# ALU.net
KiCad netlist of a schematic drawn in EAGLE
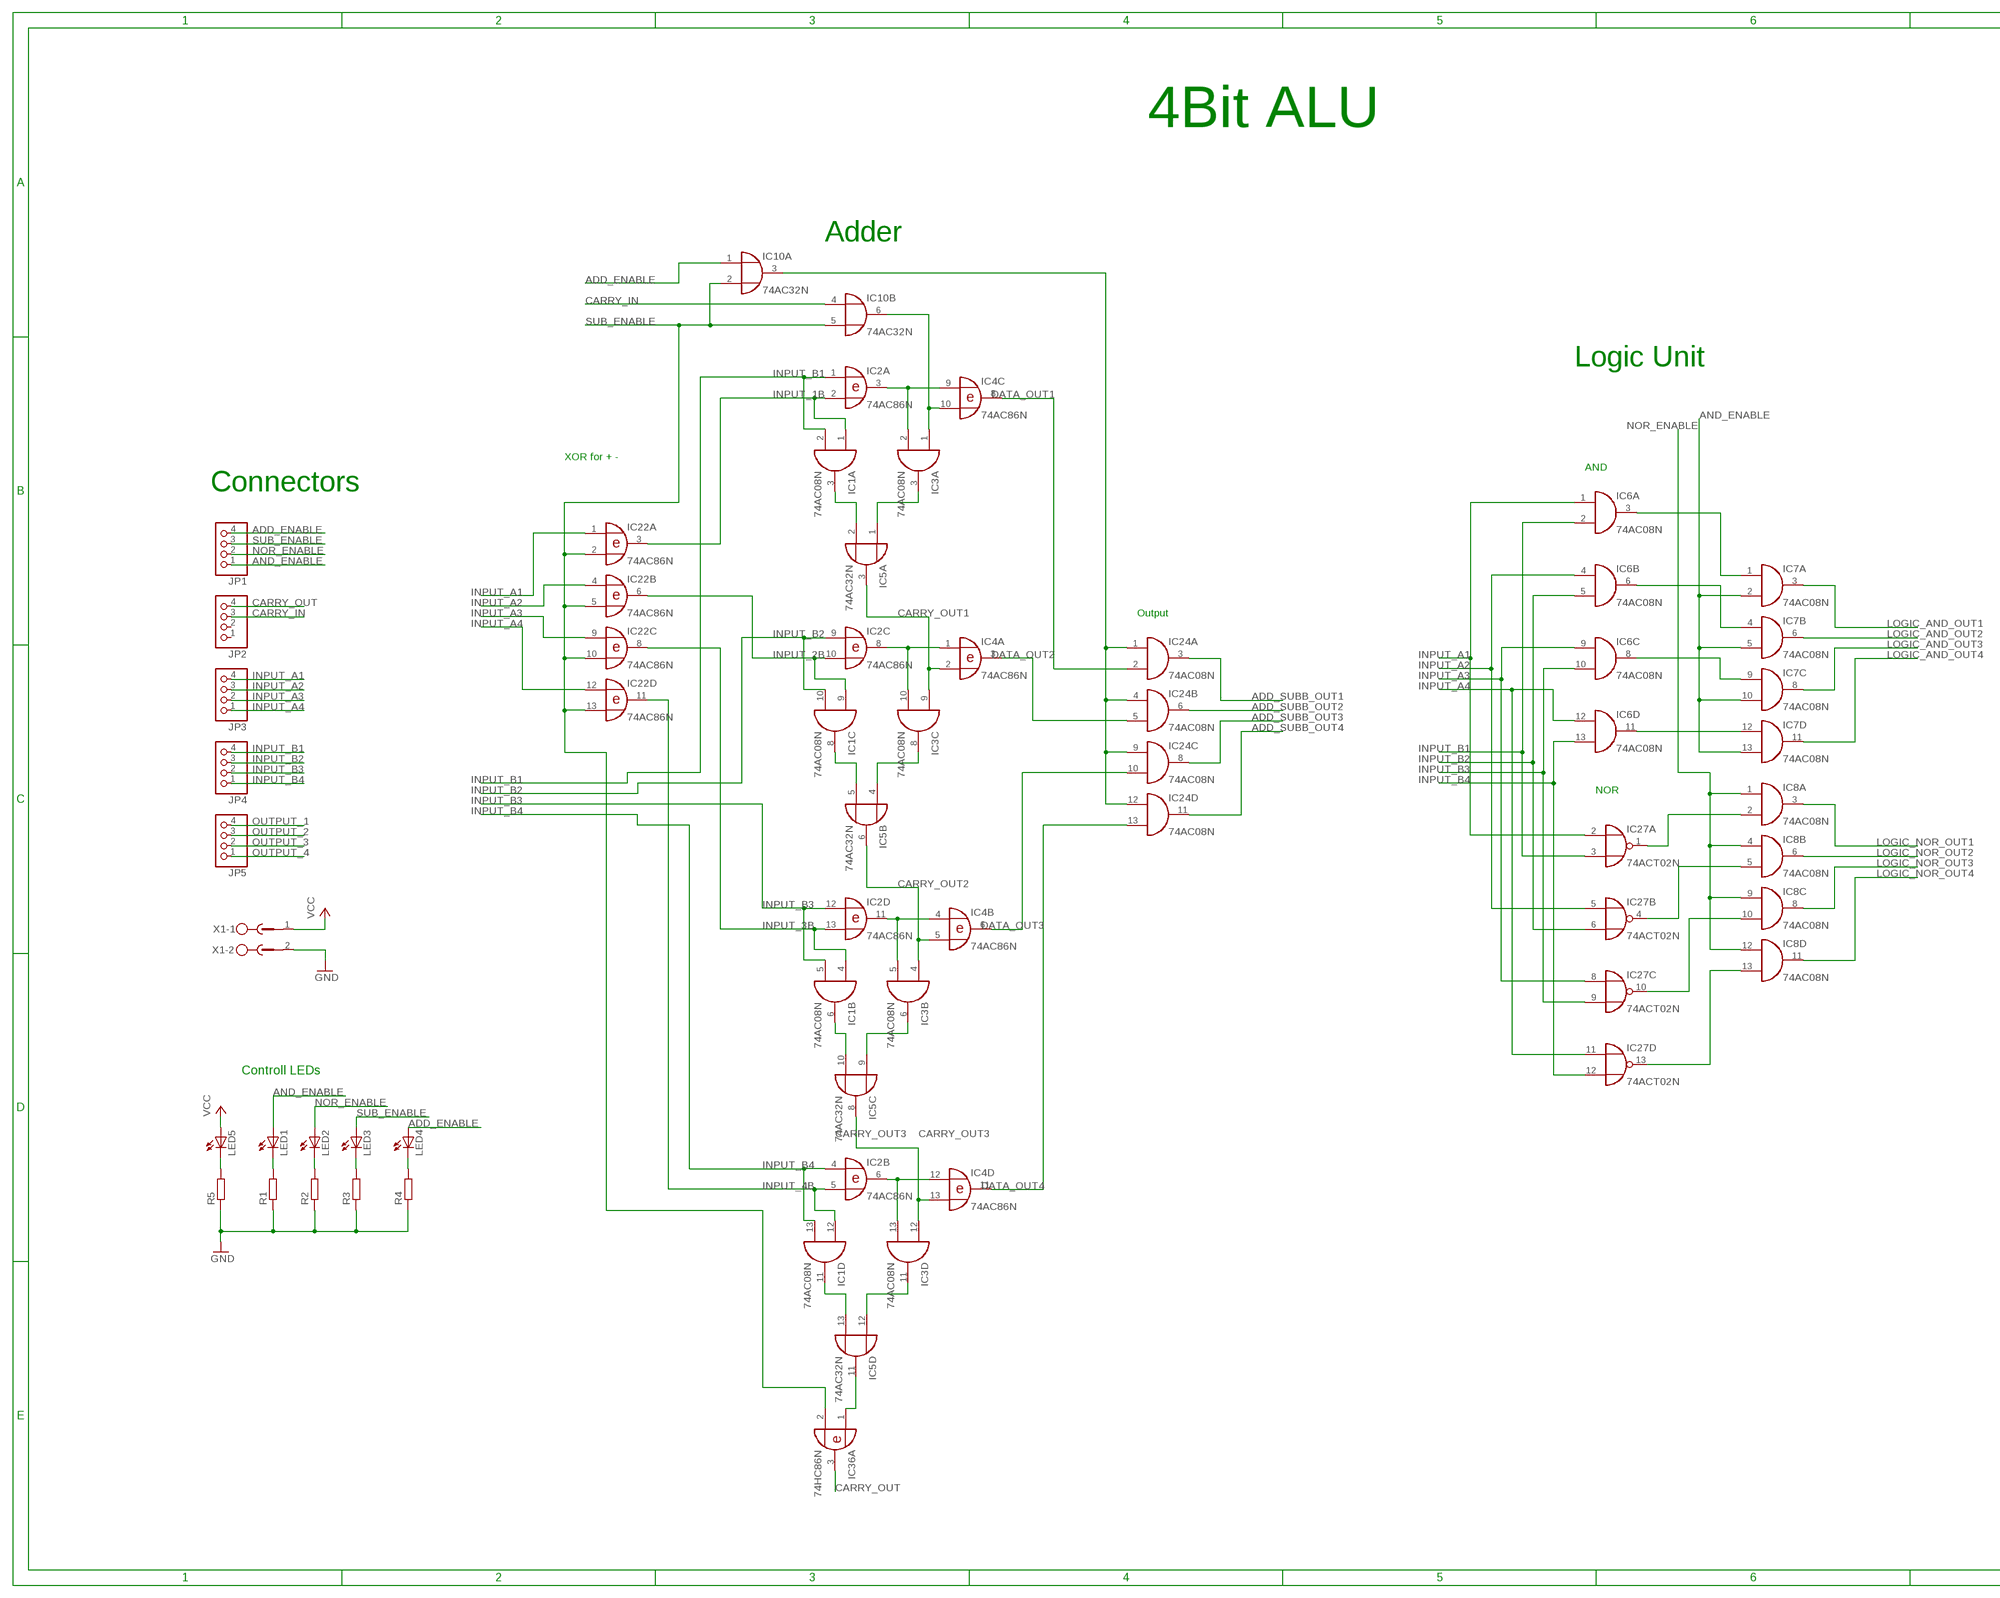
[diagram p0: schematic, sheet 1, part 1 of 2]
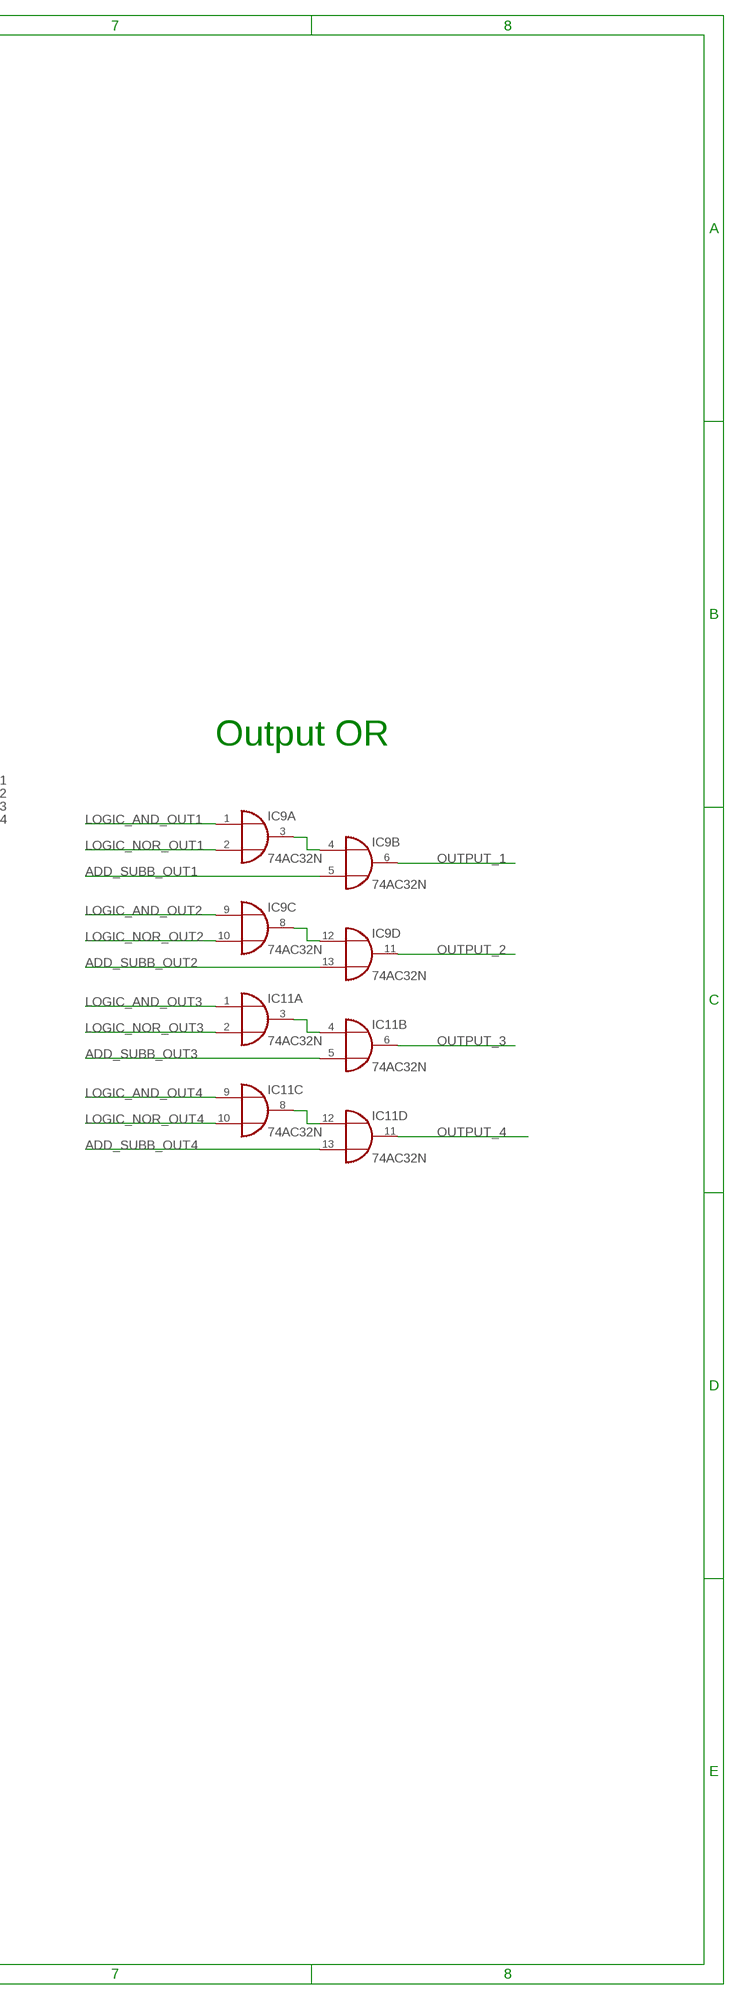
[diagram p1: schematic, sheet 1, part 2 of 2]

(export (version "E")
  (design (tool "Eeschema 10.0.6"))
  (components
    (comp (ref "IC1")
      (value "74AC08N")
      (footprint "eagle-import:DIL14")
      (libsource (lib "eagle-import") (part "7408NAC"))
    )
    (comp (ref "IC2")
      (value "74AC86N")
      (footprint "eagle-import:DIL14")
      (libsource (lib "eagle-import") (part "7486NAC"))
    )
    (comp (ref "IC3")
      (value "74AC08N")
      (footprint "eagle-import:DIL14")
      (libsource (lib "eagle-import") (part "7408NAC"))
    )
    (comp (ref "IC4")
      (value "74AC86N")
      (footprint "eagle-import:DIL14")
      (libsource (lib "eagle-import") (part "7486NAC"))
    )
    (comp (ref "IC5")
      (value "74AC32N")
      (footprint "eagle-import:DIL14")
      (libsource (lib "eagle-import") (part "7432NAC"))
    )
    (comp (ref "IC6")
      (value "74AC08N")
      (footprint "eagle-import:DIL14")
      (libsource (lib "eagle-import") (part "7408NAC"))
    )
    (comp (ref "IC7")
      (value "74AC08N")
      (footprint "eagle-import:DIL14")
      (libsource (lib "eagle-import") (part "7408NAC"))
    )
    (comp (ref "IC8")
      (value "74AC08N")
      (footprint "eagle-import:DIL14")
      (libsource (lib "eagle-import") (part "7408NAC"))
    )
    (comp (ref "IC9")
      (value "74AC32N")
      (footprint "eagle-import:DIL14")
      (libsource (lib "eagle-import") (part "7432NAC"))
    )
    (comp (ref "IC10")
      (value "74AC32N")
      (footprint "eagle-import:DIL14")
      (libsource (lib "eagle-import") (part "7432NAC"))
    )
    (comp (ref "IC11")
      (value "74AC32N")
      (footprint "eagle-import:DIL14")
      (libsource (lib "eagle-import") (part "7432NAC"))
    )
    (comp (ref "IC22")
      (value "74AC86N")
      (footprint "eagle-import:DIL14")
      (libsource (lib "eagle-import") (part "7486NAC"))
    )
    (comp (ref "IC24")
      (value "74AC08N")
      (footprint "eagle-import:DIL14")
      (libsource (lib "eagle-import") (part "7408NAC"))
    )
    (comp (ref "IC27")
      (value "74ACT02N")
      (footprint "eagle-import:DIL14")
      (libsource (lib "eagle-import") (part "7402NACT"))
    )
    (comp (ref "IC36")
      (value "74HC86N")
      (footprint "eagle-import:DIL14")
      (libsource (lib "eagle-import") (part "7486NHC"))
    )
    (comp (ref "JP1")
      (value "PINHD-1X4")
      (footprint "eagle-import:1X04")
      (libsource (lib "eagle-import") (part "PINHD-1X4"))
    )
    (comp (ref "JP2")
      (value "PINHD-1X4")
      (footprint "eagle-import:1X04")
      (libsource (lib "eagle-import") (part "PINHD-1X4"))
    )
    (comp (ref "JP3")
      (value "PINHD-1X4")
      (footprint "eagle-import:1X04")
      (libsource (lib "eagle-import") (part "PINHD-1X4"))
    )
    (comp (ref "JP4")
      (value "PINHD-1X4")
      (footprint "eagle-import:1X04")
      (libsource (lib "eagle-import") (part "PINHD-1X4"))
    )
    (comp (ref "JP5")
      (value "PINHD-1X4")
      (footprint "eagle-import:1X04")
      (libsource (lib "eagle-import") (part "PINHD-1X4"))
    )
    (comp (ref "LED1")
      (value "LED5MM")
      (footprint "eagle-import:LED5MM")
      (libsource (lib "eagle-import") (part "LED5MM"))
    )
    (comp (ref "LED2")
      (value "LED5MM")
      (footprint "eagle-import:LED5MM")
      (libsource (lib "eagle-import") (part "LED5MM"))
    )
    (comp (ref "LED3")
      (value "LED5MM")
      (footprint "eagle-import:LED5MM")
      (libsource (lib "eagle-import") (part "LED5MM"))
    )
    (comp (ref "LED4")
      (value "LED5MM")
      (footprint "eagle-import:LED5MM")
      (libsource (lib "eagle-import") (part "LED5MM"))
    )
    (comp (ref "LED5")
      (value "LED5MM")
      (footprint "eagle-import:LED5MM")
      (libsource (lib "eagle-import") (part "LED5MM"))
    )
    (comp (ref "R1")
      (value "R-EU_0204/5")
      (footprint "eagle-import:0204_5")
      (libsource (lib "eagle-import") (part "R-EU_0204/5"))
    )
    (comp (ref "R2")
      (value "R-EU_0204/5")
      (footprint "eagle-import:0204_5")
      (libsource (lib "eagle-import") (part "R-EU_0204/5"))
    )
    (comp (ref "R3")
      (value "R-EU_0204/5")
      (footprint "eagle-import:0204_5")
      (libsource (lib "eagle-import") (part "R-EU_0204/5"))
    )
    (comp (ref "R4")
      (value "R-EU_0204/5")
      (footprint "eagle-import:0204_5")
      (libsource (lib "eagle-import") (part "R-EU_0204/5"))
    )
    (comp (ref "R5")
      (value "R-EU_0204/5")
      (footprint "eagle-import:0204_5")
      (libsource (lib "eagle-import") (part "R-EU_0204/5"))
    )
    (comp (ref "X1")
      (value "MSTBV2")
      (footprint "eagle-import:MSTBV2")
      (libsource (lib "eagle-import") (part "MSTBV2"))
    )
  )
  (nets
    (net (code "1") (name "/ADD_ENABLE") (class "Default")
      (node (ref "IC10") (pin "1") (pinfunction "I0_1") (pintype "input"))
      (node (ref "JP1") (pin "4") (pinfunction "4_4") (pintype "passive"))
      (node (ref "LED4") (pin "A") (pinfunction "A_A") (pintype "passive"))
    )
    (net (code "2") (name "/ADD_SUBB_OUT1") (class "Default")
      (node (ref "IC24") (pin "3") (pinfunction "O_3") (pintype "output"))
      (node (ref "IC9") (pin "5") (pinfunction "I1_5") (pintype "input"))
    )
    (net (code "3") (name "/ADD_SUBB_OUT2") (class "Default")
      (node (ref "IC24") (pin "6") (pinfunction "O_6") (pintype "output"))
      (node (ref "IC9") (pin "13") (pinfunction "I1_13") (pintype "input"))
    )
    (net (code "4") (name "/ADD_SUBB_OUT3") (class "Default")
      (node (ref "IC11") (pin "5") (pinfunction "I1_5") (pintype "input"))
      (node (ref "IC24") (pin "8") (pinfunction "O_8") (pintype "output"))
    )
    (net (code "5") (name "/ADD_SUBB_OUT4") (class "Default")
      (node (ref "IC11") (pin "13") (pinfunction "I1_13") (pintype "input"))
      (node (ref "IC24") (pin "11") (pinfunction "O_11") (pintype "output"))
    )
    (net (code "6") (name "/AND_ENABLE") (class "Default")
      (node (ref "IC7") (pin "10") (pinfunction "I1_10") (pintype "input"))
      (node (ref "IC7") (pin "13") (pinfunction "I1_13") (pintype "input"))
      (node (ref "IC7") (pin "2") (pinfunction "I1_2") (pintype "input"))
      (node (ref "IC7") (pin "5") (pinfunction "I1_5") (pintype "input"))
      (node (ref "JP1") (pin "1") (pinfunction "1_1") (pintype "passive"))
      (node (ref "LED1") (pin "A") (pinfunction "A_A") (pintype "passive"))
    )
    (net (code "7") (name "/CARRY_IN") (class "Default")
      (node (ref "IC10") (pin "4") (pinfunction "I0_4") (pintype "input"))
      (node (ref "JP2") (pin "3") (pinfunction "3_3") (pintype "passive"))
    )
    (net (code "8") (name "/CARRY_OUT") (class "Default")
      (node (ref "IC36") (pin "3") (pinfunction "O_3") (pintype "output"))
      (node (ref "JP2") (pin "4") (pinfunction "4_4") (pintype "passive"))
    )
    (net (code "9") (name "/CARRY_OUT1") (class "Default")
      (node (ref "IC3") (pin "9") (pinfunction "I0_9") (pintype "input"))
      (node (ref "IC4") (pin "2") (pinfunction "I1_2") (pintype "input"))
      (node (ref "IC5") (pin "3") (pinfunction "O_3") (pintype "output"))
    )
    (net (code "10") (name "/CARRY_OUT2") (class "Default")
      (node (ref "IC3") (pin "4") (pinfunction "I0_4") (pintype "input"))
      (node (ref "IC4") (pin "5") (pinfunction "I1_5") (pintype "input"))
      (node (ref "IC5") (pin "6") (pinfunction "O_6") (pintype "output"))
    )
    (net (code "11") (name "/CARRY_OUT3") (class "Default")
      (node (ref "IC3") (pin "12") (pinfunction "I0_12") (pintype "input"))
      (node (ref "IC4") (pin "13") (pinfunction "I1_13") (pintype "input"))
      (node (ref "IC5") (pin "8") (pinfunction "O_8") (pintype "output"))
    )
    (net (code "12") (name "/DATA_OUT1") (class "Default")
      (node (ref "IC24") (pin "2") (pinfunction "I1_2") (pintype "input"))
      (node (ref "IC4") (pin "8") (pinfunction "O_8") (pintype "output"))
    )
    (net (code "13") (name "/DATA_OUT2") (class "Default")
      (node (ref "IC24") (pin "5") (pinfunction "I1_5") (pintype "input"))
      (node (ref "IC4") (pin "3") (pinfunction "O_3") (pintype "output"))
    )
    (net (code "14") (name "/DATA_OUT3") (class "Default")
      (node (ref "IC24") (pin "10") (pinfunction "I1_10") (pintype "input"))
      (node (ref "IC4") (pin "6") (pinfunction "O_6") (pintype "output"))
    )
    (net (code "15") (name "/DATA_OUT4") (class "Default")
      (node (ref "IC24") (pin "13") (pinfunction "I1_13") (pintype "input"))
      (node (ref "IC4") (pin "11") (pinfunction "O_11") (pintype "output"))
    )
    (net (code "16") (name "/INPUT_1B") (class "Default")
      (node (ref "IC1") (pin "1") (pinfunction "I0_1") (pintype "input"))
      (node (ref "IC2") (pin "2") (pinfunction "I1_2") (pintype "input"))
      (node (ref "IC22") (pin "3") (pinfunction "O_3") (pintype "output"))
    )
    (net (code "17") (name "/INPUT_2B") (class "Default")
      (node (ref "IC1") (pin "9") (pinfunction "I0_9") (pintype "input"))
      (node (ref "IC2") (pin "10") (pinfunction "I1_10") (pintype "input"))
      (node (ref "IC22") (pin "6") (pinfunction "O_6") (pintype "output"))
    )
    (net (code "18") (name "/INPUT_3B") (class "Default")
      (node (ref "IC1") (pin "4") (pinfunction "I0_4") (pintype "input"))
      (node (ref "IC2") (pin "13") (pinfunction "I1_13") (pintype "input"))
      (node (ref "IC22") (pin "8") (pinfunction "O_8") (pintype "output"))
    )
    (net (code "19") (name "/INPUT_4B") (class "Default")
      (node (ref "IC1") (pin "12") (pinfunction "I0_12") (pintype "input"))
      (node (ref "IC2") (pin "5") (pinfunction "I1_5") (pintype "input"))
      (node (ref "IC22") (pin "11") (pinfunction "O_11") (pintype "output"))
    )
    (net (code "20") (name "/INPUT_A1") (class "Default")
      (node (ref "IC22") (pin "1") (pinfunction "I0_1") (pintype "input"))
      (node (ref "IC27") (pin "2") (pinfunction "I0_2") (pintype "input"))
      (node (ref "IC6") (pin "1") (pinfunction "I0_1") (pintype "input"))
      (node (ref "JP3") (pin "4") (pinfunction "4_4") (pintype "passive"))
    )
    (net (code "21") (name "/INPUT_A2") (class "Default")
      (node (ref "IC22") (pin "4") (pinfunction "I0_4") (pintype "input"))
      (node (ref "IC27") (pin "5") (pinfunction "I0_5") (pintype "input"))
      (node (ref "IC6") (pin "4") (pinfunction "I0_4") (pintype "input"))
      (node (ref "JP3") (pin "3") (pinfunction "3_3") (pintype "passive"))
    )
    (net (code "22") (name "/INPUT_A3") (class "Default")
      (node (ref "IC22") (pin "9") (pinfunction "I0_9") (pintype "input"))
      (node (ref "IC27") (pin "8") (pinfunction "I0_8") (pintype "input"))
      (node (ref "IC6") (pin "9") (pinfunction "I0_9") (pintype "input"))
      (node (ref "JP3") (pin "2") (pinfunction "2_2") (pintype "passive"))
    )
    (net (code "23") (name "/INPUT_A4") (class "Default")
      (node (ref "IC22") (pin "12") (pinfunction "I0_12") (pintype "input"))
      (node (ref "IC27") (pin "11") (pinfunction "I0_11") (pintype "input"))
      (node (ref "IC6") (pin "12") (pinfunction "I0_12") (pintype "input"))
      (node (ref "JP3") (pin "1") (pinfunction "1_1") (pintype "passive"))
    )
    (net (code "24") (name "/INPUT_B1") (class "Default")
      (node (ref "IC1") (pin "2") (pinfunction "I1_2") (pintype "input"))
      (node (ref "IC2") (pin "1") (pinfunction "I0_1") (pintype "input"))
      (node (ref "IC27") (pin "3") (pinfunction "I1_3") (pintype "input"))
      (node (ref "IC6") (pin "2") (pinfunction "I1_2") (pintype "input"))
      (node (ref "JP4") (pin "4") (pinfunction "4_4") (pintype "passive"))
    )
    (net (code "25") (name "/INPUT_B2") (class "Default")
      (node (ref "IC1") (pin "10") (pinfunction "I1_10") (pintype "input"))
      (node (ref "IC2") (pin "9") (pinfunction "I0_9") (pintype "input"))
      (node (ref "IC27") (pin "6") (pinfunction "I1_6") (pintype "input"))
      (node (ref "IC6") (pin "5") (pinfunction "I1_5") (pintype "input"))
      (node (ref "JP4") (pin "3") (pinfunction "3_3") (pintype "passive"))
    )
    (net (code "26") (name "/INPUT_B3") (class "Default")
      (node (ref "IC1") (pin "5") (pinfunction "I1_5") (pintype "input"))
      (node (ref "IC2") (pin "12") (pinfunction "I0_12") (pintype "input"))
      (node (ref "IC27") (pin "9") (pinfunction "I1_9") (pintype "input"))
      (node (ref "IC6") (pin "10") (pinfunction "I1_10") (pintype "input"))
      (node (ref "JP4") (pin "2") (pinfunction "2_2") (pintype "passive"))
    )
    (net (code "27") (name "/INPUT_B4") (class "Default")
      (node (ref "IC1") (pin "13") (pinfunction "I1_13") (pintype "input"))
      (node (ref "IC2") (pin "4") (pinfunction "I0_4") (pintype "input"))
      (node (ref "IC27") (pin "12") (pinfunction "I1_12") (pintype "input"))
      (node (ref "IC6") (pin "13") (pinfunction "I1_13") (pintype "input"))
      (node (ref "JP4") (pin "1") (pinfunction "1_1") (pintype "passive"))
    )
    (net (code "28") (name "/LOGIC_AND_OUT1") (class "Default")
      (node (ref "IC7") (pin "3") (pinfunction "O_3") (pintype "output"))
      (node (ref "IC9") (pin "1") (pinfunction "I0_1") (pintype "input"))
    )
    (net (code "29") (name "/LOGIC_AND_OUT2") (class "Default")
      (node (ref "IC7") (pin "6") (pinfunction "O_6") (pintype "output"))
      (node (ref "IC9") (pin "9") (pinfunction "I0_9") (pintype "input"))
    )
    (net (code "30") (name "/LOGIC_AND_OUT3") (class "Default")
      (node (ref "IC11") (pin "1") (pinfunction "I0_1") (pintype "input"))
      (node (ref "IC7") (pin "8") (pinfunction "O_8") (pintype "output"))
    )
    (net (code "31") (name "/LOGIC_AND_OUT4") (class "Default")
      (node (ref "IC11") (pin "9") (pinfunction "I0_9") (pintype "input"))
      (node (ref "IC7") (pin "11") (pinfunction "O_11") (pintype "output"))
    )
    (net (code "32") (name "/LOGIC_NOR_OUT1") (class "Default")
      (node (ref "IC8") (pin "3") (pinfunction "O_3") (pintype "output"))
      (node (ref "IC9") (pin "2") (pinfunction "I1_2") (pintype "input"))
    )
    (net (code "33") (name "/LOGIC_NOR_OUT2") (class "Default")
      (node (ref "IC8") (pin "6") (pinfunction "O_6") (pintype "output"))
      (node (ref "IC9") (pin "10") (pinfunction "I1_10") (pintype "input"))
    )
    (net (code "34") (name "/LOGIC_NOR_OUT3") (class "Default")
      (node (ref "IC11") (pin "2") (pinfunction "I1_2") (pintype "input"))
      (node (ref "IC8") (pin "8") (pinfunction "O_8") (pintype "output"))
    )
    (net (code "35") (name "/LOGIC_NOR_OUT4") (class "Default")
      (node (ref "IC11") (pin "10") (pinfunction "I1_10") (pintype "input"))
      (node (ref "IC8") (pin "11") (pinfunction "O_11") (pintype "output"))
    )
    (net (code "36") (name "/NOR_ENABLE") (class "Default")
      (node (ref "IC8") (pin "1") (pinfunction "I0_1") (pintype "input"))
      (node (ref "IC8") (pin "12") (pinfunction "I0_12") (pintype "input"))
      (node (ref "IC8") (pin "4") (pinfunction "I0_4") (pintype "input"))
      (node (ref "IC8") (pin "9") (pinfunction "I0_9") (pintype "input"))
      (node (ref "JP1") (pin "2") (pinfunction "2_2") (pintype "passive"))
      (node (ref "LED2") (pin "A") (pinfunction "A_A") (pintype "passive"))
    )
    (net (code "37") (name "/OUTPUT_1") (class "Default")
      (node (ref "IC9") (pin "6") (pinfunction "O_6") (pintype "output"))
      (node (ref "JP5") (pin "4") (pinfunction "4_4") (pintype "passive"))
    )
    (net (code "38") (name "/OUTPUT_2") (class "Default")
      (node (ref "IC9") (pin "11") (pinfunction "O_11") (pintype "output"))
      (node (ref "JP5") (pin "3") (pinfunction "3_3") (pintype "passive"))
    )
    (net (code "39") (name "/OUTPUT_3") (class "Default")
      (node (ref "IC11") (pin "6") (pinfunction "O_6") (pintype "output"))
      (node (ref "JP5") (pin "2") (pinfunction "2_2") (pintype "passive"))
    )
    (net (code "40") (name "/OUTPUT_4") (class "Default")
      (node (ref "IC11") (pin "11") (pinfunction "O_11") (pintype "output"))
      (node (ref "JP5") (pin "1") (pinfunction "1_1") (pintype "passive"))
    )
    (net (code "41") (name "/SUB_ENABLE") (class "Default")
      (node (ref "IC10") (pin "2") (pinfunction "I1_2") (pintype "input"))
      (node (ref "IC10") (pin "5") (pinfunction "I1_5") (pintype "input"))
      (node (ref "IC22") (pin "10") (pinfunction "I1_10") (pintype "input"))
      (node (ref "IC22") (pin "13") (pinfunction "I1_13") (pintype "input"))
      (node (ref "IC22") (pin "2") (pinfunction "I1_2") (pintype "input"))
      (node (ref "IC22") (pin "5") (pinfunction "I1_5") (pintype "input"))
      (node (ref "IC36") (pin "2") (pinfunction "I1_2") (pintype "input"))
      (node (ref "JP1") (pin "3") (pinfunction "3_3") (pintype "passive"))
      (node (ref "LED3") (pin "A") (pinfunction "A_A") (pintype "passive"))
    )
    (net (code "42") (name "GND") (class "Default")
      (node (ref "R1") (pin "1") (pinfunction "1_1") (pintype "passive"))
      (node (ref "R2") (pin "1") (pinfunction "1_1") (pintype "passive"))
      (node (ref "R3") (pin "1") (pinfunction "1_1") (pintype "passive"))
      (node (ref "R4") (pin "1") (pinfunction "1_1") (pintype "passive"))
      (node (ref "R5") (pin "1") (pinfunction "1_1") (pintype "passive"))
      (node (ref "X1") (pin "2") (pinfunction "SK_2") (pintype "passive"))
    )
    (net (code "43") (name "Net-(IC1A-O)") (class "Default")
      (node (ref "IC1") (pin "3") (pinfunction "O_3") (pintype "output"))
      (node (ref "IC5") (pin "2") (pinfunction "I1_2") (pintype "input"))
    )
    (net (code "44") (name "Net-(IC1B-O)") (class "Default")
      (node (ref "IC1") (pin "6") (pinfunction "O_6") (pintype "output"))
      (node (ref "IC5") (pin "10") (pinfunction "I1_10") (pintype "input"))
    )
    (net (code "45") (name "Net-(IC1C-O)") (class "Default")
      (node (ref "IC1") (pin "8") (pinfunction "O_8") (pintype "output"))
      (node (ref "IC5") (pin "5") (pinfunction "I1_5") (pintype "input"))
    )
    (net (code "46") (name "Net-(IC1D-O)") (class "Default")
      (node (ref "IC1") (pin "11") (pinfunction "O_11") (pintype "output"))
      (node (ref "IC5") (pin "13") (pinfunction "I1_13") (pintype "input"))
    )
    (net (code "47") (name "Net-(IC2A-O)") (class "Default")
      (node (ref "IC2") (pin "3") (pinfunction "O_3") (pintype "output"))
      (node (ref "IC3") (pin "2") (pinfunction "I1_2") (pintype "input"))
      (node (ref "IC4") (pin "9") (pinfunction "I0_9") (pintype "input"))
    )
    (net (code "48") (name "Net-(IC2B-O)") (class "Default")
      (node (ref "IC2") (pin "6") (pinfunction "O_6") (pintype "output"))
      (node (ref "IC3") (pin "13") (pinfunction "I1_13") (pintype "input"))
      (node (ref "IC4") (pin "12") (pinfunction "I0_12") (pintype "input"))
    )
    (net (code "49") (name "Net-(IC2C-O)") (class "Default")
      (node (ref "IC2") (pin "8") (pinfunction "O_8") (pintype "output"))
      (node (ref "IC3") (pin "10") (pinfunction "I1_10") (pintype "input"))
      (node (ref "IC4") (pin "1") (pinfunction "I0_1") (pintype "input"))
    )
    (net (code "50") (name "Net-(IC2D-O)") (class "Default")
      (node (ref "IC2") (pin "11") (pinfunction "O_11") (pintype "output"))
      (node (ref "IC3") (pin "5") (pinfunction "I1_5") (pintype "input"))
      (node (ref "IC4") (pin "4") (pinfunction "I0_4") (pintype "input"))
    )
    (net (code "51") (name "Net-(IC3A-O)") (class "Default")
      (node (ref "IC3") (pin "3") (pinfunction "O_3") (pintype "output"))
      (node (ref "IC5") (pin "1") (pinfunction "I0_1") (pintype "input"))
    )
    (net (code "52") (name "Net-(IC3B-O)") (class "Default")
      (node (ref "IC3") (pin "6") (pinfunction "O_6") (pintype "output"))
      (node (ref "IC5") (pin "9") (pinfunction "I0_9") (pintype "input"))
    )
    (net (code "53") (name "Net-(IC3C-O)") (class "Default")
      (node (ref "IC3") (pin "8") (pinfunction "O_8") (pintype "output"))
      (node (ref "IC5") (pin "4") (pinfunction "I0_4") (pintype "input"))
    )
    (net (code "54") (name "Net-(IC3D-O)") (class "Default")
      (node (ref "IC3") (pin "11") (pinfunction "O_11") (pintype "output"))
      (node (ref "IC5") (pin "12") (pinfunction "I0_12") (pintype "input"))
    )
    (net (code "55") (name "Net-(IC6A-O)") (class "Default")
      (node (ref "IC6") (pin "3") (pinfunction "O_3") (pintype "output"))
      (node (ref "IC7") (pin "1") (pinfunction "I0_1") (pintype "input"))
    )
    (net (code "56") (name "Net-(IC6B-O)") (class "Default")
      (node (ref "IC6") (pin "6") (pinfunction "O_6") (pintype "output"))
      (node (ref "IC7") (pin "4") (pinfunction "I0_4") (pintype "input"))
    )
    (net (code "57") (name "Net-(IC6C-O)") (class "Default")
      (node (ref "IC6") (pin "8") (pinfunction "O_8") (pintype "output"))
      (node (ref "IC7") (pin "9") (pinfunction "I0_9") (pintype "input"))
    )
    (net (code "58") (name "Net-(IC6D-O)") (class "Default")
      (node (ref "IC6") (pin "11") (pinfunction "O_11") (pintype "output"))
      (node (ref "IC7") (pin "12") (pinfunction "I0_12") (pintype "input"))
    )
    (net (code "59") (name "Net-(IC9A-O)") (class "Default")
      (node (ref "IC9") (pin "3") (pinfunction "O_3") (pintype "output"))
      (node (ref "IC9") (pin "4") (pinfunction "I0_4") (pintype "input"))
    )
    (net (code "60") (name "Net-(IC9C-O)") (class "Default")
      (node (ref "IC9") (pin "12") (pinfunction "I0_12") (pintype "input"))
      (node (ref "IC9") (pin "8") (pinfunction "O_8") (pintype "output"))
    )
    (net (code "61") (name "Net-(IC10A-O)") (class "Default")
      (node (ref "IC10") (pin "3") (pinfunction "O_3") (pintype "output"))
      (node (ref "IC24") (pin "1") (pinfunction "I0_1") (pintype "input"))
      (node (ref "IC24") (pin "12") (pinfunction "I0_12") (pintype "input"))
      (node (ref "IC24") (pin "4") (pinfunction "I0_4") (pintype "input"))
      (node (ref "IC24") (pin "9") (pinfunction "I0_9") (pintype "input"))
    )
    (net (code "62") (name "Net-(IC10B-O)") (class "Default")
      (node (ref "IC10") (pin "6") (pinfunction "O_6") (pintype "output"))
      (node (ref "IC3") (pin "1") (pinfunction "I0_1") (pintype "input"))
      (node (ref "IC4") (pin "10") (pinfunction "I1_10") (pintype "input"))
    )
    (net (code "63") (name "Net-(IC11A-O)") (class "Default")
      (node (ref "IC11") (pin "3") (pinfunction "O_3") (pintype "output"))
      (node (ref "IC11") (pin "4") (pinfunction "I0_4") (pintype "input"))
    )
    (net (code "64") (name "Net-(IC11C-O)") (class "Default")
      (node (ref "IC11") (pin "12") (pinfunction "I0_12") (pintype "input"))
      (node (ref "IC11") (pin "8") (pinfunction "O_8") (pintype "output"))
    )
    (net (code "65") (name "Net-(IC27A-O)") (class "Default")
      (node (ref "IC27") (pin "1") (pinfunction "O_1") (pintype "output"))
      (node (ref "IC8") (pin "2") (pinfunction "I1_2") (pintype "input"))
    )
    (net (code "66") (name "Net-(IC27B-O)") (class "Default")
      (node (ref "IC27") (pin "4") (pinfunction "O_4") (pintype "output"))
      (node (ref "IC8") (pin "5") (pinfunction "I1_5") (pintype "input"))
    )
    (net (code "67") (name "Net-(IC27C-O)") (class "Default")
      (node (ref "IC27") (pin "10") (pinfunction "O_10") (pintype "output"))
      (node (ref "IC8") (pin "10") (pinfunction "I1_10") (pintype "input"))
    )
    (net (code "68") (name "Net-(IC27D-O)") (class "Default")
      (node (ref "IC27") (pin "13") (pinfunction "O_13") (pintype "output"))
      (node (ref "IC8") (pin "13") (pinfunction "I1_13") (pintype "input"))
    )
    (net (code "69") (name "Net-(IC36A-I0)") (class "Default")
      (node (ref "IC36") (pin "1") (pinfunction "I0_1") (pintype "input"))
      (node (ref "IC5") (pin "11") (pinfunction "O_11") (pintype "output"))
    )
    (net (code "70") (name "Net-(LED1-C)") (class "Default")
      (node (ref "LED1") (pin "K") (pinfunction "C_K") (pintype "passive"))
      (node (ref "R1") (pin "2") (pinfunction "2_2") (pintype "passive"))
    )
    (net (code "71") (name "Net-(LED2-C)") (class "Default")
      (node (ref "LED2") (pin "K") (pinfunction "C_K") (pintype "passive"))
      (node (ref "R2") (pin "2") (pinfunction "2_2") (pintype "passive"))
    )
    (net (code "72") (name "Net-(LED3-C)") (class "Default")
      (node (ref "LED3") (pin "K") (pinfunction "C_K") (pintype "passive"))
      (node (ref "R3") (pin "2") (pinfunction "2_2") (pintype "passive"))
    )
    (net (code "73") (name "Net-(LED4-C)") (class "Default")
      (node (ref "LED4") (pin "K") (pinfunction "C_K") (pintype "passive"))
      (node (ref "R4") (pin "2") (pinfunction "2_2") (pintype "passive"))
    )
    (net (code "74") (name "Net-(LED5-C)") (class "Default")
      (node (ref "LED5") (pin "K") (pinfunction "C_K") (pintype "passive"))
      (node (ref "R5") (pin "2") (pinfunction "2_2") (pintype "passive"))
    )
    (net (code "75") (name "VCC") (class "Default")
      (node (ref "LED5") (pin "A") (pinfunction "A_A") (pintype "passive"))
      (node (ref "X1") (pin "1") (pinfunction "SK_1") (pintype "passive"))
    )
    (net (code "76") (name "unconnected-(JP2-Pad1)") (class "Default")
      (node (ref "JP2") (pin "1") (pinfunction "1_1") (pintype "passive"))
    )
    (net (code "77") (name "unconnected-(JP2-Pad2)") (class "Default")
      (node (ref "JP2") (pin "2") (pinfunction "2_2") (pintype "passive"))
    )
  )
)
